# 05_POW_LD.net
KiCad netlist of a schematic drawn in Altium Designer
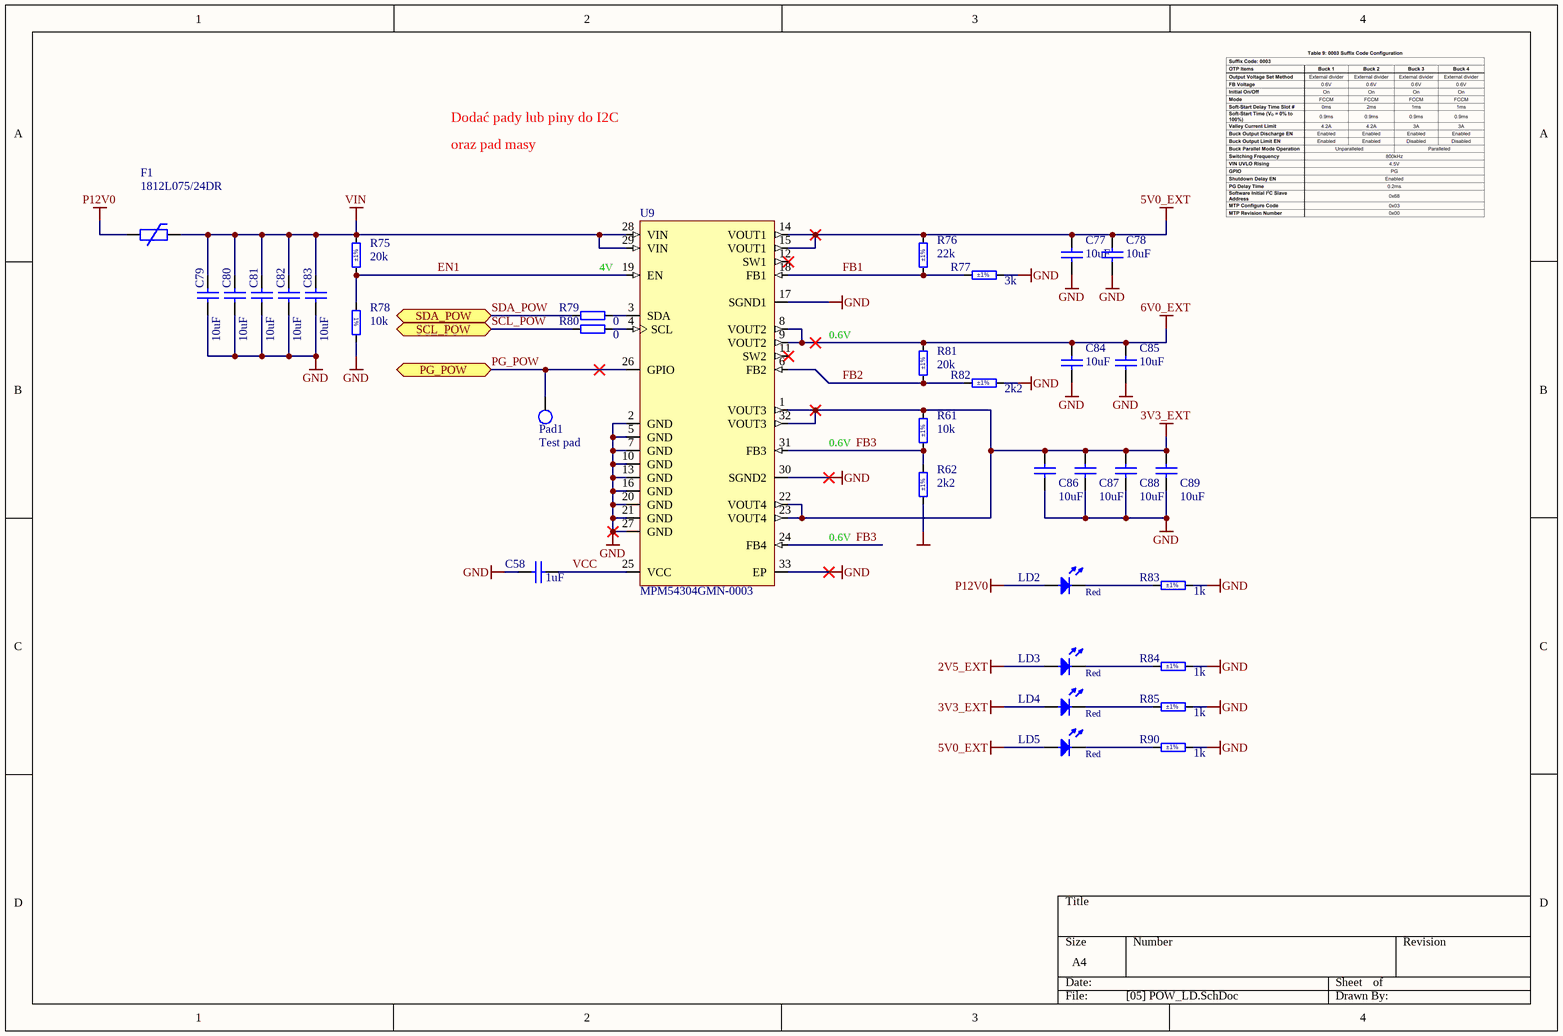
[diagram p0: [05] POW_LD.SchDoc]

(export (version "E")
  (design (tool "Eeschema 10.0.6"))
  (components
    (comp (ref "C58")
      (value "1uF")
      (footprint "CAPC1005X55N")
      (description "Non-polarised capacitor")
      (fields
        (field (name "PART NUMBER") "CC0402_1UF_25V_10%_X5R")
        (field (name "VOLTAGE") "25V")
        (field (name "AUTHOR") "CERN DEM BC")
      )
      (libsource (lib "Capacitors") (part "Capacitor - non polarized"))
    )
    (comp (ref "C77")
      (value "10uF")
      (footprint "CAPC2012X145N")
      (description "Non-polarised capacitor")
      (fields
        (field (name "PART NUMBER") "CC0805_10UF_25V_10%_X7R")
        (field (name "VOLTAGE") "25V")
        (field (name "AUTHOR") "CERN DEM HF")
      )
      (libsource (lib "Capacitors") (part "Capacitor - non polarized"))
    )
    (comp (ref "C78")
      (value "10uF")
      (footprint "CAPC2012X145N")
      (description "Non-polarised capacitor")
      (fields
        (field (name "PART NUMBER") "CC0805_10UF_25V_10%_X7R")
        (field (name "VOLTAGE") "25V")
        (field (name "AUTHOR") "CERN DEM HF")
      )
      (libsource (lib "Capacitors") (part "Capacitor - non polarized"))
    )
    (comp (ref "C79")
      (value "10uF")
      (footprint "CAPC2012X145N")
      (description "Non-polarised capacitor")
      (fields
        (field (name "PART NUMBER") "CC0805_10UF_25V_10%_X7R")
        (field (name "VOLTAGE") "25V")
        (field (name "AUTHOR") "CERN DEM HF")
      )
      (libsource (lib "Capacitors") (part "Capacitor - non polarized"))
    )
    (comp (ref "C80")
      (value "10uF")
      (footprint "CAPC2012X145N")
      (description "Non-polarised capacitor")
      (fields
        (field (name "PART NUMBER") "CC0805_10UF_25V_10%_X7R")
        (field (name "VOLTAGE") "25V")
        (field (name "AUTHOR") "CERN DEM HF")
      )
      (libsource (lib "Capacitors") (part "Capacitor - non polarized"))
    )
    (comp (ref "C81")
      (value "10uF")
      (footprint "CAPC2012X145N")
      (description "Non-polarised capacitor")
      (fields
        (field (name "PART NUMBER") "CC0805_10UF_25V_10%_X7R")
        (field (name "VOLTAGE") "25V")
        (field (name "AUTHOR") "CERN DEM HF")
      )
      (libsource (lib "Capacitors") (part "Capacitor - non polarized"))
    )
    (comp (ref "C82")
      (value "10uF")
      (footprint "CAPC2012X145N")
      (description "Non-polarised capacitor")
      (fields
        (field (name "PART NUMBER") "CC0805_10UF_25V_10%_X7R")
        (field (name "VOLTAGE") "25V")
        (field (name "AUTHOR") "CERN DEM HF")
      )
      (libsource (lib "Capacitors") (part "Capacitor - non polarized"))
    )
    (comp (ref "C83")
      (value "10uF")
      (footprint "CAPC2012X145N")
      (description "Non-polarised capacitor")
      (fields
        (field (name "PART NUMBER") "CC0805_10UF_25V_10%_X7R")
        (field (name "VOLTAGE") "25V")
        (field (name "AUTHOR") "CERN DEM HF")
      )
      (libsource (lib "Capacitors") (part "Capacitor - non polarized"))
    )
    (comp (ref "C84")
      (value "10uF")
      (footprint "CAPC2012X145N")
      (description "Non-polarised capacitor")
      (fields
        (field (name "PART NUMBER") "CC0805_10UF_25V_10%_X7R")
        (field (name "VOLTAGE") "25V")
        (field (name "AUTHOR") "CERN DEM HF")
      )
      (libsource (lib "Capacitors") (part "Capacitor - non polarized"))
    )
    (comp (ref "C85")
      (value "10uF")
      (footprint "CAPC2012X145N")
      (description "Non-polarised capacitor")
      (fields
        (field (name "PART NUMBER") "CC0805_10UF_25V_10%_X7R")
        (field (name "VOLTAGE") "25V")
        (field (name "AUTHOR") "CERN DEM HF")
      )
      (libsource (lib "Capacitors") (part "Capacitor - non polarized"))
    )
    (comp (ref "C86")
      (value "10uF")
      (footprint "CAPC2012X145N")
      (description "Non-polarised capacitor")
      (fields
        (field (name "PART NUMBER") "CC0805_10UF_25V_10%_X7R")
        (field (name "VOLTAGE") "25V")
        (field (name "AUTHOR") "CERN DEM HF")
      )
      (libsource (lib "Capacitors") (part "Capacitor - non polarized"))
    )
    (comp (ref "C87")
      (value "10uF")
      (footprint "CAPC2012X145N")
      (description "Non-polarised capacitor")
      (fields
        (field (name "PART NUMBER") "CC0805_10UF_25V_10%_X7R")
        (field (name "VOLTAGE") "25V")
        (field (name "AUTHOR") "CERN DEM HF")
      )
      (libsource (lib "Capacitors") (part "Capacitor - non polarized"))
    )
    (comp (ref "C88")
      (value "10uF")
      (footprint "CAPC2012X145N")
      (description "Non-polarised capacitor")
      (fields
        (field (name "PART NUMBER") "CC0805_10UF_25V_10%_X7R")
        (field (name "VOLTAGE") "25V")
        (field (name "AUTHOR") "CERN DEM HF")
      )
      (libsource (lib "Capacitors") (part "Capacitor - non polarized"))
    )
    (comp (ref "C89")
      (value "10uF")
      (footprint "CAPC2012X145N")
      (description "Non-polarised capacitor")
      (fields
        (field (name "PART NUMBER") "CC0805_10UF_25V_10%_X7R")
        (field (name "VOLTAGE") "25V")
        (field (name "AUTHOR") "CERN DEM HF")
      )
      (libsource (lib "Capacitors") (part "Capacitor - non polarized"))
    )
    (comp (ref "F1")
      (value "1812L075/24DR")
      (footprint "F0805")
      (description "Bezpiecznik: polimerowy PTC; 750mA; 1812L")
      (libsource (lib "Component Library 3.2") (part "1812L075"))
    )
    (comp (ref "LD2")
      (value "Red")
      (footprint "LED_KINGBRIGHT_KP-1608SURCK")
      (description "LED Red 1C 2A")
      (fields
        (field (name "PART NUMBER") "LED_KINGBRIGHT_KP-1608SURCK")
        (field (name "MANUFACTURER") "KINGBRIGHT")
        (field (name "AUTHOR") "CERN DEM HF")
      )
      (libsource (lib "ICs And Semiconductors") (part "LED Red 1C 2A"))
    )
    (comp (ref "LD3")
      (value "Red")
      (footprint "LED_KINGBRIGHT_KP-1608SURCK")
      (description "LED Red 1C 2A")
      (fields
        (field (name "PART NUMBER") "LED_KINGBRIGHT_KP-1608SURCK")
        (field (name "MANUFACTURER") "KINGBRIGHT")
        (field (name "AUTHOR") "CERN DEM HF")
      )
      (libsource (lib "ICs And Semiconductors") (part "LED Red 1C 2A"))
    )
    (comp (ref "LD4")
      (value "Red")
      (footprint "LED_KINGBRIGHT_KP-1608SURCK")
      (description "LED Red 1C 2A")
      (fields
        (field (name "PART NUMBER") "LED_KINGBRIGHT_KP-1608SURCK")
        (field (name "MANUFACTURER") "KINGBRIGHT")
        (field (name "AUTHOR") "CERN DEM HF")
      )
      (libsource (lib "ICs And Semiconductors") (part "LED Red 1C 2A"))
    )
    (comp (ref "LD5")
      (value "Red")
      (footprint "LED_KINGBRIGHT_KP-1608SURCK")
      (description "LED Red 1C 2A")
      (fields
        (field (name "PART NUMBER") "LED_KINGBRIGHT_KP-1608SURCK")
        (field (name "MANUFACTURER") "KINGBRIGHT")
        (field (name "AUTHOR") "CERN DEM HF")
      )
      (libsource (lib "ICs And Semiconductors") (part "LED Red 1C 2A"))
    )
    (comp (ref "Pad1")
      (value "Test pad")
      (footprint "Pad 1mm")
      (libsource (lib "Component Library 3.2") (part "Test pad"))
    )
    (comp (ref "R61")
      (value "10k")
      (footprint "RESC1005X40N")
      (description "Resistor - 1%")
      (fields
        (field (name "TOLERANCE") "±1%")
        (field (name "PART NUMBER") "R0402_10K_1%_0.0625W_100PPM")
        (field (name "POWER") "0.0625W")
        (field (name "AUTHOR") "CERN DEM JLC")
      )
      (libsource (lib "Resistors") (part "Resistor - 1%"))
    )
    (comp (ref "R62")
      (value "2k2")
      (footprint "RESC1005X40N")
      (description "Resistor - 1%")
      (fields
        (field (name "TOLERANCE") "±1%")
        (field (name "PART NUMBER") "R0402_2K2_1%_0.0625W_100PPM")
        (field (name "POWER") "0.0625W")
        (field (name "AUTHOR") "CERN DEM JLC")
      )
      (libsource (lib "Resistors") (part "Resistor - 1%"))
    )
    (comp (ref "R75")
      (value "20k")
      (footprint "RESC1005X40N")
      (description "Resistor - 1%")
      (fields
        (field (name "TOLERANCE") "±1%")
        (field (name "PART NUMBER") "R0402_20K_1%_0.0625W_100PPM")
        (field (name "POWER") "0.0625W")
        (field (name "AUTHOR") "CERN DEM JLC")
      )
      (libsource (lib "Resistors") (part "Resistor - 1%"))
    )
    (comp (ref "R76")
      (value "22k")
      (footprint "RESC1005X40N")
      (description "Resistor - 1%")
      (fields
        (field (name "TOLERANCE") "±1%")
        (field (name "PART NUMBER") "R0402_22K_1%_0.0625W_100PPM")
        (field (name "POWER") "0.0625W")
        (field (name "AUTHOR") "CERN DEM JLC")
      )
      (libsource (lib "Resistors") (part "Resistor - 1%"))
    )
    (comp (ref "R77")
      (value "3k")
      (footprint "RESC1005X40N")
      (description "Resistor - 1%")
      (fields
        (field (name "TOLERANCE") "±1%")
        (field (name "PART NUMBER") "R0402_3K_1%_0.0625W_100PPM")
        (field (name "POWER") "0.0625W")
        (field (name "AUTHOR") "CERN DEM JLC")
      )
      (libsource (lib "Resistors") (part "Resistor - 1%"))
    )
    (comp (ref "R78")
      (value "10k")
      (footprint "RESC1005X40N")
      (description "Resistor - 1%")
      (fields
        (field (name "PART NUMBER") "R0402_10K_1%_0.0625W_100PPM")
        (field (name "POWER") "0.0625W")
        (field (name "AUTHOR") "CERN DEM JLC")
      )
      (libsource (lib "Resistors") (part "Resistor - 1%"))
    )
    (comp (ref "R79")
      (value "0")
      (footprint "RESC1005X40N")
      (description "Resistor")
      (fields
        (field (name "PART NUMBER") "R0402_0R_JUMPER")
        (field (name "MANUFACTURER") "GENERIC")
        (field (name "AUTHOR") "CERN DEM JLC")
      )
      (libsource (lib "Resistors") (part "Resistor"))
    )
    (comp (ref "R80")
      (value "0")
      (footprint "RESC1005X40N")
      (description "Resistor")
      (fields
        (field (name "PART NUMBER") "R0402_0R_JUMPER")
        (field (name "MANUFACTURER") "GENERIC")
        (field (name "AUTHOR") "CERN DEM JLC")
      )
      (libsource (lib "Resistors") (part "Resistor"))
    )
    (comp (ref "R81")
      (value "20k")
      (footprint "RESC1005X40N")
      (description "Resistor - 1%")
      (fields
        (field (name "TOLERANCE") "±1%")
        (field (name "PART NUMBER") "R0402_20K_1%_0.0625W_100PPM")
        (field (name "POWER") "0.0625W")
        (field (name "AUTHOR") "CERN DEM JLC")
      )
      (libsource (lib "Resistors") (part "Resistor - 1%"))
    )
    (comp (ref "R82")
      (value "2k2")
      (footprint "RESC1005X40N")
      (description "Resistor - 1%")
      (fields
        (field (name "TOLERANCE") "±1%")
        (field (name "PART NUMBER") "R0402_2K2_1%_0.0625W_100PPM")
        (field (name "POWER") "0.0625W")
        (field (name "AUTHOR") "CERN DEM JLC")
      )
      (libsource (lib "Resistors") (part "Resistor - 1%"))
    )
    (comp (ref "R83")
      (value "1k")
      (footprint "RESC1005X40N")
      (description "Resistor - 1%")
      (fields
        (field (name "TOLERANCE") "±1%")
        (field (name "PART NUMBER") "R0402_1K_1%_0.0625W_100PPM")
        (field (name "POWER") "0.0625W")
        (field (name "AUTHOR") "CERN DEM JLC")
      )
      (libsource (lib "Resistors") (part "Resistor - 1%"))
    )
    (comp (ref "R84")
      (value "1k")
      (footprint "RESC1005X40N")
      (description "Resistor - 1%")
      (fields
        (field (name "TOLERANCE") "±1%")
        (field (name "PART NUMBER") "R0402_1K_1%_0.0625W_100PPM")
        (field (name "POWER") "0.0625W")
        (field (name "AUTHOR") "CERN DEM JLC")
      )
      (libsource (lib "Resistors") (part "Resistor - 1%"))
    )
    (comp (ref "R85")
      (value "1k")
      (footprint "RESC1005X40N")
      (description "Resistor - 1%")
      (fields
        (field (name "TOLERANCE") "±1%")
        (field (name "PART NUMBER") "R0402_1K_1%_0.0625W_100PPM")
        (field (name "POWER") "0.0625W")
        (field (name "AUTHOR") "CERN DEM JLC")
      )
      (libsource (lib "Resistors") (part "Resistor - 1%"))
    )
    (comp (ref "R90")
      (value "1k")
      (footprint "RESC1005X40N")
      (description "Resistor - 1%")
      (fields
        (field (name "TOLERANCE") "±1%")
        (field (name "PART NUMBER") "R0402_1K_1%_0.0625W_100PPM")
        (field (name "POWER") "0.0625W")
        (field (name "AUTHOR") "CERN DEM JLC")
      )
      (libsource (lib "Resistors") (part "Resistor - 1%"))
    )
    (comp (ref "U9")
      (value "MPM54304GMN-0003")
      (footprint "PowerFLGA-33")
      (description "Buck Switching Regulator IC Positive Adjustable 0.55V 4 Output 2A, 3A 33-PowerFLGA Module")
      (libsource (lib "Component Library 3.2") (part "MPM54304GMN-0003"))
    )
  )
  (nets
    (net (code "1") (name "/EN1") (class "Default")
      (node (ref "R75") (pin "2") (pinfunction "2_2") (pintype "passive"))
      (node (ref "R78") (pin "1") (pinfunction "1_1") (pintype "passive"))
      (node (ref "U9") (pin "19") (pinfunction "EN_19") (pintype "input"))
    )
    (net (code "2") (name "/FB1") (class "Default")
      (node (ref "R76") (pin "1") (pinfunction "1_1") (pintype "passive"))
      (node (ref "R77") (pin "1") (pinfunction "1_1") (pintype "passive"))
      (node (ref "U9") (pin "18") (pinfunction "FB1_18") (pintype "input"))
    )
    (net (code "3") (name "/FB2") (class "Default")
      (node (ref "R81") (pin "2") (pinfunction "2_2") (pintype "passive"))
      (node (ref "R82") (pin "1") (pinfunction "1_1") (pintype "passive"))
      (node (ref "U9") (pin "6") (pinfunction "FB2_6") (pintype "input"))
    )
    (net (code "4") (name "/FB3") (class "Default")
      (node (ref "R61") (pin "1") (pinfunction "1_1") (pintype "passive"))
      (node (ref "R62") (pin "2") (pinfunction "2_2") (pintype "passive"))
      (node (ref "U9") (pin "24") (pinfunction "FB4_24") (pintype "input"))
      (node (ref "U9") (pin "31") (pinfunction "FB3_31") (pintype "input"))
    )
    (net (code "5") (name "/PG_POW") (class "Default")
      (node (ref "Pad1") (pin "1") (pinfunction "1_1") (pintype "passive"))
      (node (ref "U9") (pin "26") (pinfunction "GPIO_26") (pintype "bidirectional"))
    )
    (net (code "6") (name "/SCL_POW") (class "Default")
      (node (ref "R80") (pin "1") (pinfunction "1_1") (pintype "passive"))
    )
    (net (code "7") (name "/SDA_POW") (class "Default")
      (node (ref "R79") (pin "1") (pinfunction "1_1") (pintype "passive"))
    )
    (net (code "8") (name "/VCC") (class "Default")
      (node (ref "C58") (pin "1") (pinfunction "1_1") (pintype "passive"))
      (node (ref "U9") (pin "25") (pinfunction "VCC_25") (pintype "power_in"))
    )
    (net (code "9") (name "2V5_EXT") (class "Default")
      (node (ref "LD3") (pin "2") (pinfunction "A_2") (pintype "passive"))
    )
    (net (code "10") (name "3V3_EXT") (class "Default")
      (node (ref "C86") (pin "2") (pinfunction "2_2") (pintype "passive"))
      (node (ref "C87") (pin "2") (pinfunction "2_2") (pintype "passive"))
      (node (ref "C88") (pin "2") (pinfunction "2_2") (pintype "passive"))
      (node (ref "C89") (pin "2") (pinfunction "2_2") (pintype "passive"))
      (node (ref "LD4") (pin "2") (pinfunction "A_2") (pintype "passive"))
      (node (ref "R61") (pin "2") (pinfunction "2_2") (pintype "passive"))
      (node (ref "U9") (pin "1") (pinfunction "VOUT3_1") (pintype "output"))
      (node (ref "U9") (pin "22") (pinfunction "VOUT4_22") (pintype "output"))
      (node (ref "U9") (pin "23") (pinfunction "VOUT4_23") (pintype "output"))
      (node (ref "U9") (pin "32") (pinfunction "VOUT3_32") (pintype "output"))
    )
    (net (code "11") (name "5V0_EXT") (class "Default")
      (node (ref "C77") (pin "2") (pinfunction "2_2") (pintype "passive"))
      (node (ref "C78") (pin "2") (pinfunction "2_2") (pintype "passive"))
      (node (ref "LD5") (pin "2") (pinfunction "A_2") (pintype "passive"))
      (node (ref "R76") (pin "2") (pinfunction "2_2") (pintype "passive"))
      (node (ref "U9") (pin "14") (pinfunction "VOUT1_14") (pintype "output"))
      (node (ref "U9") (pin "15") (pinfunction "VOUT1_15") (pintype "output"))
    )
    (net (code "12") (name "6V0_EXT") (class "Default")
      (node (ref "C84") (pin "2") (pinfunction "2_2") (pintype "passive"))
      (node (ref "C85") (pin "2") (pinfunction "2_2") (pintype "passive"))
      (node (ref "R81") (pin "1") (pinfunction "1_1") (pintype "passive"))
      (node (ref "U9") (pin "8") (pinfunction "VOUT2_8") (pintype "output"))
      (node (ref "U9") (pin "9") (pinfunction "VOUT2_9") (pintype "output"))
    )
    (net (code "13") (name "GND") (class "Default")
      (node (ref "C58") (pin "2") (pinfunction "2_2") (pintype "passive"))
      (node (ref "C77") (pin "1") (pinfunction "1_1") (pintype "passive"))
      (node (ref "C78") (pin "1") (pinfunction "1_1") (pintype "passive"))
      (node (ref "C79") (pin "1") (pinfunction "1_1") (pintype "passive"))
      (node (ref "C80") (pin "1") (pinfunction "1_1") (pintype "passive"))
      (node (ref "C81") (pin "1") (pinfunction "1_1") (pintype "passive"))
      (node (ref "C82") (pin "1") (pinfunction "1_1") (pintype "passive"))
      (node (ref "C83") (pin "1") (pinfunction "1_1") (pintype "passive"))
      (node (ref "C84") (pin "1") (pinfunction "1_1") (pintype "passive"))
      (node (ref "C85") (pin "1") (pinfunction "1_1") (pintype "passive"))
      (node (ref "C86") (pin "1") (pinfunction "1_1") (pintype "passive"))
      (node (ref "C87") (pin "1") (pinfunction "1_1") (pintype "passive"))
      (node (ref "C88") (pin "1") (pinfunction "1_1") (pintype "passive"))
      (node (ref "C89") (pin "1") (pinfunction "1_1") (pintype "passive"))
      (node (ref "R62") (pin "1") (pinfunction "1_1") (pintype "passive"))
      (node (ref "R77") (pin "2") (pinfunction "2_2") (pintype "passive"))
      (node (ref "R78") (pin "2") (pinfunction "2_2") (pintype "passive"))
      (node (ref "R82") (pin "2") (pinfunction "2_2") (pintype "passive"))
      (node (ref "R83") (pin "2") (pinfunction "2_2") (pintype "passive"))
      (node (ref "R84") (pin "2") (pinfunction "2_2") (pintype "passive"))
      (node (ref "R85") (pin "2") (pinfunction "2_2") (pintype "passive"))
      (node (ref "R90") (pin "2") (pinfunction "2_2") (pintype "passive"))
      (node (ref "U9") (pin "10") (pinfunction "GND_10") (pintype "power_in"))
      (node (ref "U9") (pin "13") (pinfunction "GND_13") (pintype "power_in"))
      (node (ref "U9") (pin "16") (pinfunction "GND_16") (pintype "power_in"))
      (node (ref "U9") (pin "17") (pinfunction "SGND1_17") (pintype "power_in"))
      (node (ref "U9") (pin "2") (pinfunction "GND_2") (pintype "power_in"))
      (node (ref "U9") (pin "20") (pinfunction "GND_20") (pintype "power_in"))
      (node (ref "U9") (pin "21") (pinfunction "GND_21") (pintype "power_in"))
      (node (ref "U9") (pin "27") (pinfunction "GND_27") (pintype "power_in"))
      (node (ref "U9") (pin "30") (pinfunction "SGND2_30") (pintype "power_in"))
      (node (ref "U9") (pin "33") (pinfunction "EP_33") (pintype "power_in"))
      (node (ref "U9") (pin "5") (pinfunction "GND_5") (pintype "power_in"))
      (node (ref "U9") (pin "7") (pinfunction "GND_7") (pintype "power_in"))
    )
    (net (code "14") (name "Net-(LD2-C)") (class "Default")
      (node (ref "LD2") (pin "1") (pinfunction "C_1") (pintype "passive"))
      (node (ref "R83") (pin "1") (pinfunction "1_1") (pintype "passive"))
    )
    (net (code "15") (name "Net-(LD3-C)") (class "Default")
      (node (ref "LD3") (pin "1") (pinfunction "C_1") (pintype "passive"))
      (node (ref "R84") (pin "1") (pinfunction "1_1") (pintype "passive"))
    )
    (net (code "16") (name "Net-(LD4-C)") (class "Default")
      (node (ref "LD4") (pin "1") (pinfunction "C_1") (pintype "passive"))
      (node (ref "R85") (pin "1") (pinfunction "1_1") (pintype "passive"))
    )
    (net (code "17") (name "Net-(LD5-C)") (class "Default")
      (node (ref "LD5") (pin "1") (pinfunction "C_1") (pintype "passive"))
      (node (ref "R90") (pin "1") (pinfunction "1_1") (pintype "passive"))
    )
    (net (code "18") (name "Net-(U9-SCL)") (class "Default")
      (node (ref "R80") (pin "2") (pinfunction "2_2") (pintype "passive"))
      (node (ref "U9") (pin "4") (pinfunction "SCL_4") (pintype "input"))
    )
    (net (code "19") (name "Net-(U9-SDA)") (class "Default")
      (node (ref "R79") (pin "2") (pinfunction "2_2") (pintype "passive"))
      (node (ref "U9") (pin "3") (pinfunction "SDA_3") (pintype "bidirectional"))
    )
    (net (code "20") (name "P12V0") (class "Default")
      (node (ref "F1") (pin "1") (pinfunction "1_1") (pintype "passive"))
      (node (ref "LD2") (pin "2") (pinfunction "A_2") (pintype "passive"))
    )
    (net (code "21") (name "VIN") (class "Default")
      (node (ref "C79") (pin "2") (pinfunction "2_2") (pintype "passive"))
      (node (ref "C80") (pin "2") (pinfunction "2_2") (pintype "passive"))
      (node (ref "C81") (pin "2") (pinfunction "2_2") (pintype "passive"))
      (node (ref "C82") (pin "2") (pinfunction "2_2") (pintype "passive"))
      (node (ref "C83") (pin "2") (pinfunction "2_2") (pintype "passive"))
      (node (ref "F1") (pin "2") (pinfunction "2_2") (pintype "passive"))
      (node (ref "R75") (pin "1") (pinfunction "1_1") (pintype "passive"))
      (node (ref "U9") (pin "28") (pinfunction "VIN_28") (pintype "input"))
      (node (ref "U9") (pin "29") (pinfunction "VIN_29") (pintype "input"))
    )
    (net (code "22") (name "unconnected-(U9-SW1-Pad12)") (class "Default")
      (node (ref "U9") (pin "12") (pinfunction "SW1_12") (pintype "output+no_connect"))
    )
    (net (code "23") (name "unconnected-(U9-SW2-Pad11)") (class "Default")
      (node (ref "U9") (pin "11") (pinfunction "SW2_11") (pintype "output+no_connect"))
    )
  )
)
